# Panelize_-_Xonik_Noise_A6_w_logo_v2_0.net
KiCad netlist of a schematic drawn in EAGLE
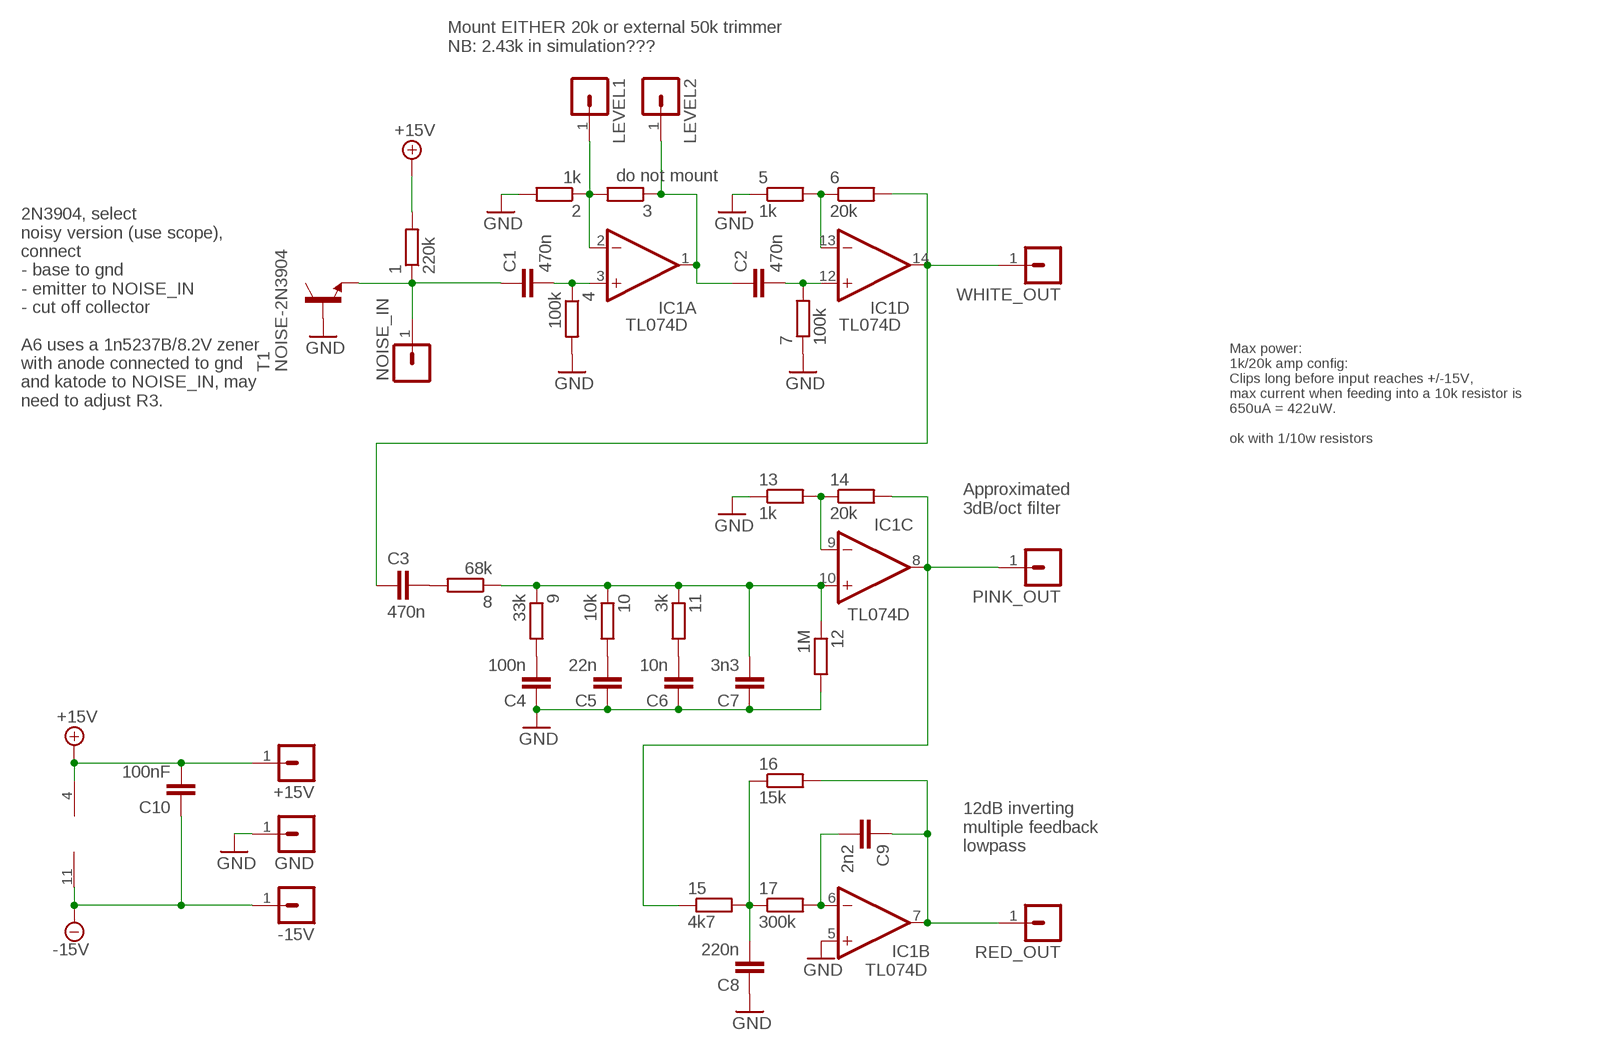
[diagram p0: schematic, sheet 1]

(export (version "E")
  (design (tool "Eeschema 10.0.6"))
  (components
    (comp (ref "+15V")
      (value "MA01-1JP")
      (footprint "eagle-import:SIP-PIN01-1J")
      (libsource (lib "eagle-import") (part "MA01-1JP"))
    )
    (comp (ref "-15V")
      (value "MA01-1JP")
      (footprint "eagle-import:SIP-PIN01-1J")
      (libsource (lib "eagle-import") (part "MA01-1JP"))
    )
    (comp (ref "1")
      (value "220k")
      (footprint "eagle-import:R0805")
      (libsource (lib "eagle-import") (part "R-EU_R0805"))
    )
    (comp (ref "2")
      (value "1k")
      (footprint "eagle-import:R0805")
      (libsource (lib "eagle-import") (part "R-EU_R0805"))
    )
    (comp (ref "3")
      (value "do not mount")
      (footprint "eagle-import:R0805")
      (libsource (lib "eagle-import") (part "R-EU_R0805"))
    )
    (comp (ref "4")
      (value "100k")
      (footprint "eagle-import:R0805")
      (libsource (lib "eagle-import") (part "R-EU_R0805"))
    )
    (comp (ref "5")
      (value "1k")
      (footprint "eagle-import:R0805")
      (libsource (lib "eagle-import") (part "R-EU_R0805"))
    )
    (comp (ref "6")
      (value "20k")
      (footprint "eagle-import:R0805")
      (libsource (lib "eagle-import") (part "R-EU_R0805"))
    )
    (comp (ref "7")
      (value "100k")
      (footprint "eagle-import:R0805")
      (libsource (lib "eagle-import") (part "R-EU_R0805"))
    )
    (comp (ref "8")
      (value "68k")
      (footprint "eagle-import:R0805")
      (libsource (lib "eagle-import") (part "R-EU_R0805"))
    )
    (comp (ref "9")
      (value "33k")
      (footprint "eagle-import:R0805")
      (libsource (lib "eagle-import") (part "R-EU_R0805"))
    )
    (comp (ref "10")
      (value "10k")
      (footprint "eagle-import:R0805")
      (libsource (lib "eagle-import") (part "R-EU_R0805"))
    )
    (comp (ref "11")
      (value "3k")
      (footprint "eagle-import:R0805")
      (libsource (lib "eagle-import") (part "R-EU_R0805"))
    )
    (comp (ref "12")
      (value "1M")
      (footprint "eagle-import:R0805")
      (libsource (lib "eagle-import") (part "R-EU_R0805"))
    )
    (comp (ref "13")
      (value "1k")
      (footprint "eagle-import:R0805")
      (libsource (lib "eagle-import") (part "R-EU_R0805"))
    )
    (comp (ref "14")
      (value "20k")
      (footprint "eagle-import:R0805")
      (libsource (lib "eagle-import") (part "R-EU_R0805"))
    )
    (comp (ref "15")
      (value "4k7")
      (footprint "eagle-import:R0805")
      (libsource (lib "eagle-import") (part "R-EU_R0805"))
    )
    (comp (ref "16")
      (value "15k")
      (footprint "eagle-import:R0805")
      (libsource (lib "eagle-import") (part "R-EU_R0805"))
    )
    (comp (ref "17")
      (value "300k")
      (footprint "eagle-import:R0805")
      (libsource (lib "eagle-import") (part "R-EU_R0805"))
    )
    (comp (ref "C1")
      (value "470n")
      (footprint "eagle-import:C0805")
      (libsource (lib "eagle-import") (part "C-EUC0805"))
    )
    (comp (ref "C2")
      (value "470n")
      (footprint "eagle-import:C0805")
      (libsource (lib "eagle-import") (part "C-EUC0805"))
    )
    (comp (ref "C3")
      (value "470n")
      (footprint "eagle-import:C0805")
      (libsource (lib "eagle-import") (part "C-EUC0805"))
    )
    (comp (ref "C4")
      (value "100n")
      (footprint "eagle-import:C0805")
      (libsource (lib "eagle-import") (part "C-EUC0805"))
    )
    (comp (ref "C5")
      (value "22n")
      (footprint "eagle-import:C0805")
      (libsource (lib "eagle-import") (part "C-EUC0805"))
    )
    (comp (ref "C6")
      (value "10n")
      (footprint "eagle-import:C0805")
      (libsource (lib "eagle-import") (part "C-EUC0805"))
    )
    (comp (ref "C7")
      (value "3n3")
      (footprint "eagle-import:C0805")
      (libsource (lib "eagle-import") (part "C-EUC0805"))
    )
    (comp (ref "C8")
      (value "220n")
      (footprint "eagle-import:C0805")
      (libsource (lib "eagle-import") (part "C-EUC0805"))
    )
    (comp (ref "C9")
      (value "2n2")
      (footprint "eagle-import:C0805")
      (libsource (lib "eagle-import") (part "C-EUC0805"))
    )
    (comp (ref "C10")
      (value "100nF")
      (footprint "eagle-import:C0603")
      (libsource (lib "eagle-import") (part "C-EUC0603"))
    )
    (comp (ref "GND")
      (value "MA01-1JP")
      (footprint "eagle-import:SIP-PIN01-1J")
      (libsource (lib "eagle-import") (part "MA01-1JP"))
    )
    (comp (ref "IC1")
      (value "TL074D")
      (footprint "eagle-import:SO14")
      (libsource (lib "eagle-import") (part "TL074D"))
    )
    (comp (ref "LEVEL1")
      (value "MA01-1JP")
      (footprint "eagle-import:SIP-PIN01-1J")
      (libsource (lib "eagle-import") (part "MA01-1JP"))
    )
    (comp (ref "LEVEL2")
      (value "MA01-1JP")
      (footprint "eagle-import:SIP-PIN01-1J")
      (libsource (lib "eagle-import") (part "MA01-1JP"))
    )
    (comp (ref "NOISE_IN")
      (value "MA01-1JP")
      (footprint "eagle-import:SIP-PIN01-1J")
      (libsource (lib "eagle-import") (part "MA01-1JP"))
    )
    (comp (ref "PINK_OUT")
      (value "MA01-1JP")
      (footprint "eagle-import:SIP-PIN01-1J")
      (libsource (lib "eagle-import") (part "MA01-1JP"))
    )
    (comp (ref "RED_OUT")
      (value "MA01-1JP")
      (footprint "eagle-import:SIP-PIN01-1J")
      (libsource (lib "eagle-import") (part "MA01-1JP"))
    )
    (comp (ref "T1")
      (value "NOISE-2N3904")
      (footprint "eagle-import:NOISE-2N3904-J")
      (libsource (lib "eagle-import") (part "NOISE-2N3904"))
    )
    (comp (ref "WHITE_OUT")
      (value "MA01-1JP")
      (footprint "eagle-import:SIP-PIN01-1J")
      (libsource (lib "eagle-import") (part "MA01-1JP"))
    )
  )
  (nets
    (net (code "1") (name "+15V") (class "Default")
      (node (ref "+15V") (pin "1") (pinfunction "1_1") (pintype "passive"))
      (node (ref "1") (pin "2") (pinfunction "2_2") (pintype "passive"))
      (node (ref "C10") (pin "2") (pinfunction "2_2") (pintype "passive"))
      (node (ref "IC1") (pin "4") (pinfunction "V+_4") (pintype "power_in"))
    )
    (net (code "2") (name "-15V") (class "Default")
      (node (ref "-15V") (pin "1") (pinfunction "1_1") (pintype "passive"))
      (node (ref "C10") (pin "1") (pinfunction "1_1") (pintype "passive"))
      (node (ref "IC1") (pin "11") (pinfunction "V-_11") (pintype "power_in"))
    )
    (net (code "3") (name "GND") (class "Default")
      (node (ref "12") (pin "2") (pinfunction "2_2") (pintype "passive"))
      (node (ref "13") (pin "1") (pinfunction "1_1") (pintype "passive"))
      (node (ref "2") (pin "2") (pinfunction "2_2") (pintype "passive"))
      (node (ref "4") (pin "2") (pinfunction "2_2") (pintype "passive"))
      (node (ref "5") (pin "1") (pinfunction "1_1") (pintype "passive"))
      (node (ref "7") (pin "1") (pinfunction "1_1") (pintype "passive"))
      (node (ref "C4") (pin "1") (pinfunction "1_1") (pintype "passive"))
      (node (ref "C5") (pin "1") (pinfunction "1_1") (pintype "passive"))
      (node (ref "C6") (pin "1") (pinfunction "1_1") (pintype "passive"))
      (node (ref "C7") (pin "1") (pinfunction "1_1") (pintype "passive"))
      (node (ref "C8") (pin "1") (pinfunction "1_1") (pintype "passive"))
      (node (ref "GND") (pin "1") (pinfunction "1_1") (pintype "passive"))
      (node (ref "IC1") (pin "5") (pinfunction "+IN_5") (pintype "input"))
      (node (ref "T1") (pin "B") (pinfunction "B_B") (pintype "passive"))
    )
    (net (code "4") (name "Net-(1-Pad1)") (class "Default")
      (node (ref "1") (pin "1") (pinfunction "1_1") (pintype "passive"))
      (node (ref "C1") (pin "1") (pinfunction "1_1") (pintype "passive"))
      (node (ref "NOISE_IN") (pin "1") (pinfunction "1_1") (pintype "passive"))
      (node (ref "T1") (pin "E") (pinfunction "E_E") (pintype "passive"))
    )
    (net (code "5") (name "Net-(8-Pad2)") (class "Default")
      (node (ref "8") (pin "2") (pinfunction "2_2") (pintype "passive"))
      (node (ref "C3") (pin "2") (pinfunction "2_2") (pintype "passive"))
    )
    (net (code "6") (name "Net-(9-Pad2)") (class "Default")
      (node (ref "9") (pin "2") (pinfunction "2_2") (pintype "passive"))
      (node (ref "C4") (pin "2") (pinfunction "2_2") (pintype "passive"))
    )
    (net (code "7") (name "Net-(10-Pad2)") (class "Default")
      (node (ref "10") (pin "2") (pinfunction "2_2") (pintype "passive"))
      (node (ref "C5") (pin "2") (pinfunction "2_2") (pintype "passive"))
    )
    (net (code "8") (name "Net-(11-Pad2)") (class "Default")
      (node (ref "11") (pin "2") (pinfunction "2_2") (pintype "passive"))
      (node (ref "C6") (pin "2") (pinfunction "2_2") (pintype "passive"))
    )
    (net (code "9") (name "Net-(15-Pad2)") (class "Default")
      (node (ref "15") (pin "2") (pinfunction "2_2") (pintype "passive"))
      (node (ref "16") (pin "1") (pinfunction "1_1") (pintype "passive"))
      (node (ref "17") (pin "1") (pinfunction "1_1") (pintype "passive"))
      (node (ref "C8") (pin "2") (pinfunction "2_2") (pintype "passive"))
    )
    (net (code "10") (name "Net-(IC1A-+IN)") (class "Default")
      (node (ref "4") (pin "1") (pinfunction "1_1") (pintype "passive"))
      (node (ref "C1") (pin "2") (pinfunction "2_2") (pintype "passive"))
      (node (ref "IC1") (pin "3") (pinfunction "+IN_3") (pintype "input"))
    )
    (net (code "11") (name "Net-(IC1A--IN)") (class "Default")
      (node (ref "2") (pin "1") (pinfunction "1_1") (pintype "passive"))
      (node (ref "3") (pin "2") (pinfunction "2_2") (pintype "passive"))
      (node (ref "IC1") (pin "2") (pinfunction "-IN_2") (pintype "input"))
      (node (ref "LEVEL1") (pin "1") (pinfunction "1_1") (pintype "passive"))
    )
    (net (code "12") (name "Net-(IC1A-OUT)") (class "Default")
      (node (ref "3") (pin "1") (pinfunction "1_1") (pintype "passive"))
      (node (ref "C2") (pin "1") (pinfunction "1_1") (pintype "passive"))
      (node (ref "IC1") (pin "1") (pinfunction "OUT_1") (pintype "output"))
      (node (ref "LEVEL2") (pin "1") (pinfunction "1_1") (pintype "passive"))
    )
    (net (code "13") (name "Net-(IC1B--IN)") (class "Default")
      (node (ref "17") (pin "2") (pinfunction "2_2") (pintype "passive"))
      (node (ref "C9") (pin "2") (pinfunction "2_2") (pintype "passive"))
      (node (ref "IC1") (pin "6") (pinfunction "-IN_6") (pintype "input"))
    )
    (net (code "14") (name "Net-(IC1B-OUT)") (class "Default")
      (node (ref "16") (pin "2") (pinfunction "2_2") (pintype "passive"))
      (node (ref "C9") (pin "1") (pinfunction "1_1") (pintype "passive"))
      (node (ref "IC1") (pin "7") (pinfunction "OUT_7") (pintype "output"))
      (node (ref "RED_OUT") (pin "1") (pinfunction "1_1") (pintype "passive"))
    )
    (net (code "15") (name "Net-(IC1C-+IN)") (class "Default")
      (node (ref "10") (pin "1") (pinfunction "1_1") (pintype "passive"))
      (node (ref "11") (pin "1") (pinfunction "1_1") (pintype "passive"))
      (node (ref "12") (pin "1") (pinfunction "1_1") (pintype "passive"))
      (node (ref "8") (pin "1") (pinfunction "1_1") (pintype "passive"))
      (node (ref "9") (pin "1") (pinfunction "1_1") (pintype "passive"))
      (node (ref "C7") (pin "2") (pinfunction "2_2") (pintype "passive"))
      (node (ref "IC1") (pin "10") (pinfunction "+IN_10") (pintype "input"))
    )
    (net (code "16") (name "Net-(IC1C--IN)") (class "Default")
      (node (ref "13") (pin "2") (pinfunction "2_2") (pintype "passive"))
      (node (ref "14") (pin "1") (pinfunction "1_1") (pintype "passive"))
      (node (ref "IC1") (pin "9") (pinfunction "-IN_9") (pintype "input"))
    )
    (net (code "17") (name "Net-(IC1C-OUT)") (class "Default")
      (node (ref "14") (pin "2") (pinfunction "2_2") (pintype "passive"))
      (node (ref "15") (pin "1") (pinfunction "1_1") (pintype "passive"))
      (node (ref "IC1") (pin "8") (pinfunction "OUT_8") (pintype "output"))
      (node (ref "PINK_OUT") (pin "1") (pinfunction "1_1") (pintype "passive"))
    )
    (net (code "18") (name "Net-(IC1D-+IN)") (class "Default")
      (node (ref "7") (pin "2") (pinfunction "2_2") (pintype "passive"))
      (node (ref "C2") (pin "2") (pinfunction "2_2") (pintype "passive"))
      (node (ref "IC1") (pin "12") (pinfunction "+IN_12") (pintype "input"))
    )
    (net (code "19") (name "Net-(IC1D--IN)") (class "Default")
      (node (ref "5") (pin "2") (pinfunction "2_2") (pintype "passive"))
      (node (ref "6") (pin "1") (pinfunction "1_1") (pintype "passive"))
      (node (ref "IC1") (pin "13") (pinfunction "-IN_13") (pintype "input"))
    )
    (net (code "20") (name "Net-(IC1D-OUT)") (class "Default")
      (node (ref "6") (pin "2") (pinfunction "2_2") (pintype "passive"))
      (node (ref "C3") (pin "1") (pinfunction "1_1") (pintype "passive"))
      (node (ref "IC1") (pin "14") (pinfunction "OUT_14") (pintype "output"))
      (node (ref "WHITE_OUT") (pin "1") (pinfunction "1_1") (pintype "passive"))
    )
  )
)
